# ProtoBricks_4x4.net
KiCad netlist of a schematic drawn in EAGLE
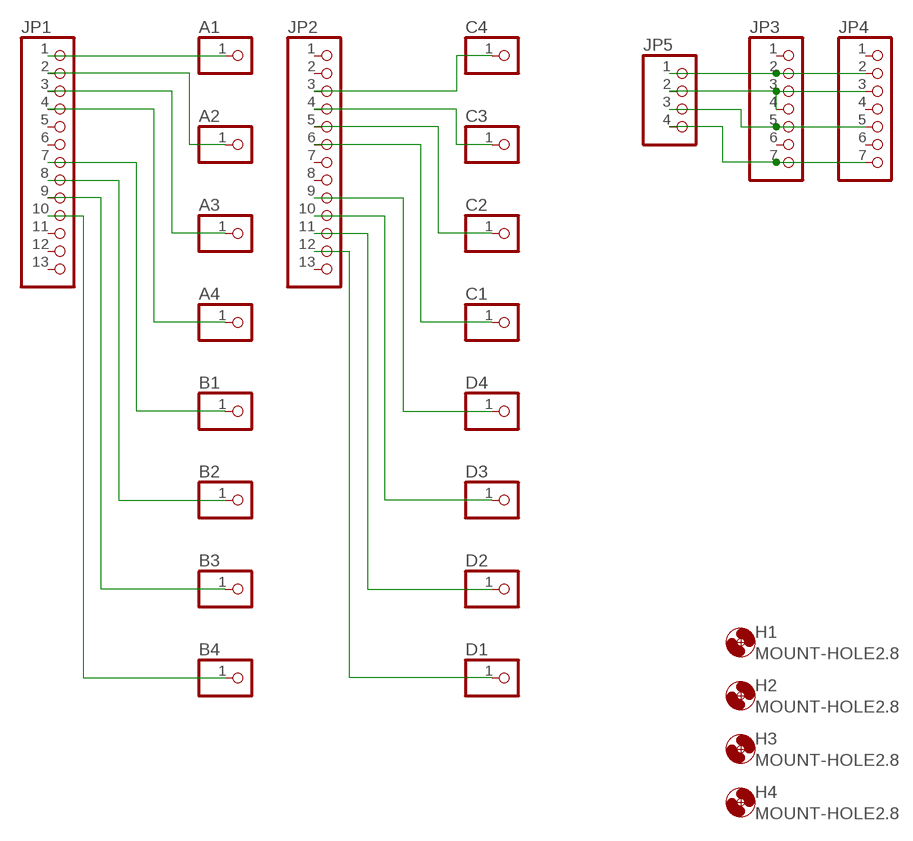
[diagram p0: schematic, sheet 1]

(export (version "E")
  (design (tool "Eeschema 10.0.6"))
  (components
    (comp (ref "A1")
      (value "PINHD-1X1")
      (footprint "eagle-import:1X01")
      (libsource (lib "eagle-import") (part "PINHD-1X1"))
    )
    (comp (ref "A2")
      (value "PINHD-1X1")
      (footprint "eagle-import:1X01")
      (libsource (lib "eagle-import") (part "PINHD-1X1"))
    )
    (comp (ref "A3")
      (value "PINHD-1X1")
      (footprint "eagle-import:1X01")
      (libsource (lib "eagle-import") (part "PINHD-1X1"))
    )
    (comp (ref "A4")
      (value "PINHD-1X1")
      (footprint "eagle-import:1X01")
      (libsource (lib "eagle-import") (part "PINHD-1X1"))
    )
    (comp (ref "B1")
      (value "PINHD-1X1")
      (footprint "eagle-import:1X01")
      (libsource (lib "eagle-import") (part "PINHD-1X1"))
    )
    (comp (ref "B2")
      (value "PINHD-1X1")
      (footprint "eagle-import:1X01")
      (libsource (lib "eagle-import") (part "PINHD-1X1"))
    )
    (comp (ref "B3")
      (value "PINHD-1X1")
      (footprint "eagle-import:1X01")
      (libsource (lib "eagle-import") (part "PINHD-1X1"))
    )
    (comp (ref "B4")
      (value "PINHD-1X1")
      (footprint "eagle-import:1X01")
      (libsource (lib "eagle-import") (part "PINHD-1X1"))
    )
    (comp (ref "C1")
      (value "PINHD-1X1")
      (footprint "eagle-import:1X01")
      (libsource (lib "eagle-import") (part "PINHD-1X1"))
    )
    (comp (ref "C2")
      (value "PINHD-1X1")
      (footprint "eagle-import:1X01")
      (libsource (lib "eagle-import") (part "PINHD-1X1"))
    )
    (comp (ref "C3")
      (value "PINHD-1X1")
      (footprint "eagle-import:1X01")
      (libsource (lib "eagle-import") (part "PINHD-1X1"))
    )
    (comp (ref "C4")
      (value "PINHD-1X1")
      (footprint "eagle-import:1X01")
      (libsource (lib "eagle-import") (part "PINHD-1X1"))
    )
    (comp (ref "D1")
      (value "PINHD-1X1")
      (footprint "eagle-import:1X01")
      (libsource (lib "eagle-import") (part "PINHD-1X1"))
    )
    (comp (ref "D2")
      (value "PINHD-1X1")
      (footprint "eagle-import:1X01")
      (libsource (lib "eagle-import") (part "PINHD-1X1"))
    )
    (comp (ref "D3")
      (value "PINHD-1X1")
      (footprint "eagle-import:1X01")
      (libsource (lib "eagle-import") (part "PINHD-1X1"))
    )
    (comp (ref "D4")
      (value "PINHD-1X1")
      (footprint "eagle-import:1X01")
      (libsource (lib "eagle-import") (part "PINHD-1X1"))
    )
    (comp (ref "H1")
      (value "MOUNT-HOLE2.8")
      (footprint "eagle-import:2,8")
      (libsource (lib "eagle-import") (part "MOUNT-HOLE2.8"))
    )
    (comp (ref "H2")
      (value "MOUNT-HOLE2.8")
      (footprint "eagle-import:2,8")
      (libsource (lib "eagle-import") (part "MOUNT-HOLE2.8"))
    )
    (comp (ref "H3")
      (value "MOUNT-HOLE2.8")
      (footprint "eagle-import:2,8")
      (libsource (lib "eagle-import") (part "MOUNT-HOLE2.8"))
    )
    (comp (ref "H4")
      (value "MOUNT-HOLE2.8")
      (footprint "eagle-import:2,8")
      (libsource (lib "eagle-import") (part "MOUNT-HOLE2.8"))
    )
    (comp (ref "JP1")
      (value "PINHD-1X13")
      (footprint "eagle-import:1X13")
      (libsource (lib "eagle-import") (part "PINHD-1X13"))
    )
    (comp (ref "JP2")
      (value "PINHD-1X13")
      (footprint "eagle-import:1X13")
      (libsource (lib "eagle-import") (part "PINHD-1X13"))
    )
    (comp (ref "JP3")
      (value "PINHD-1X7")
      (footprint "eagle-import:1X07")
      (libsource (lib "eagle-import") (part "PINHD-1X7"))
    )
    (comp (ref "JP4")
      (value "PINHD-1X7")
      (footprint "eagle-import:1X07")
      (libsource (lib "eagle-import") (part "PINHD-1X7"))
    )
    (comp (ref "JP5")
      (value "PINHD-1X4")
      (footprint "eagle-import:1X04")
      (libsource (lib "eagle-import") (part "PINHD-1X4"))
    )
  )
  (nets
    (net (code "1") (name "Net-(A1-Pad1)") (class "Default")
      (node (ref "A1") (pin "1") (pinfunction "1_1") (pintype "passive"))
      (node (ref "JP1") (pin "1") (pinfunction "1_1") (pintype "passive"))
    )
    (net (code "2") (name "Net-(A2-Pad1)") (class "Default")
      (node (ref "A2") (pin "1") (pinfunction "1_1") (pintype "passive"))
      (node (ref "JP1") (pin "2") (pinfunction "2_2") (pintype "passive"))
    )
    (net (code "3") (name "Net-(A3-Pad1)") (class "Default")
      (node (ref "A3") (pin "1") (pinfunction "1_1") (pintype "passive"))
      (node (ref "JP1") (pin "3") (pinfunction "3_3") (pintype "passive"))
    )
    (net (code "4") (name "Net-(A4-Pad1)") (class "Default")
      (node (ref "A4") (pin "1") (pinfunction "1_1") (pintype "passive"))
      (node (ref "JP1") (pin "4") (pinfunction "4_4") (pintype "passive"))
    )
    (net (code "5") (name "Net-(B1-Pad1)") (class "Default")
      (node (ref "B1") (pin "1") (pinfunction "1_1") (pintype "passive"))
      (node (ref "JP1") (pin "7") (pinfunction "7_7") (pintype "passive"))
    )
    (net (code "6") (name "Net-(B2-Pad1)") (class "Default")
      (node (ref "B2") (pin "1") (pinfunction "1_1") (pintype "passive"))
      (node (ref "JP1") (pin "8") (pinfunction "8_8") (pintype "passive"))
    )
    (net (code "7") (name "Net-(B3-Pad1)") (class "Default")
      (node (ref "B3") (pin "1") (pinfunction "1_1") (pintype "passive"))
      (node (ref "JP1") (pin "9") (pinfunction "9_9") (pintype "passive"))
    )
    (net (code "8") (name "Net-(B4-Pad1)") (class "Default")
      (node (ref "B4") (pin "1") (pinfunction "1_1") (pintype "passive"))
      (node (ref "JP1") (pin "10") (pinfunction "10_10") (pintype "passive"))
    )
    (net (code "9") (name "Net-(C1-Pad1)") (class "Default")
      (node (ref "C1") (pin "1") (pinfunction "1_1") (pintype "passive"))
      (node (ref "JP2") (pin "6") (pinfunction "6_6") (pintype "passive"))
    )
    (net (code "10") (name "Net-(C2-Pad1)") (class "Default")
      (node (ref "C2") (pin "1") (pinfunction "1_1") (pintype "passive"))
      (node (ref "JP2") (pin "5") (pinfunction "5_5") (pintype "passive"))
    )
    (net (code "11") (name "Net-(C3-Pad1)") (class "Default")
      (node (ref "C3") (pin "1") (pinfunction "1_1") (pintype "passive"))
      (node (ref "JP2") (pin "4") (pinfunction "4_4") (pintype "passive"))
    )
    (net (code "12") (name "Net-(C4-Pad1)") (class "Default")
      (node (ref "C4") (pin "1") (pinfunction "1_1") (pintype "passive"))
      (node (ref "JP2") (pin "3") (pinfunction "3_3") (pintype "passive"))
    )
    (net (code "13") (name "Net-(D1-Pad1)") (class "Default")
      (node (ref "D1") (pin "1") (pinfunction "1_1") (pintype "passive"))
      (node (ref "JP2") (pin "12") (pinfunction "12_12") (pintype "passive"))
    )
    (net (code "14") (name "Net-(D2-Pad1)") (class "Default")
      (node (ref "D2") (pin "1") (pinfunction "1_1") (pintype "passive"))
      (node (ref "JP2") (pin "11") (pinfunction "11_11") (pintype "passive"))
    )
    (net (code "15") (name "Net-(D3-Pad1)") (class "Default")
      (node (ref "D3") (pin "1") (pinfunction "1_1") (pintype "passive"))
      (node (ref "JP2") (pin "10") (pinfunction "10_10") (pintype "passive"))
    )
    (net (code "16") (name "Net-(D4-Pad1)") (class "Default")
      (node (ref "D4") (pin "1") (pinfunction "1_1") (pintype "passive"))
      (node (ref "JP2") (pin "9") (pinfunction "9_9") (pintype "passive"))
    )
    (net (code "17") (name "Net-(JP3-Pad2)") (class "Default")
      (node (ref "JP3") (pin "2") (pinfunction "2_2") (pintype "passive"))
      (node (ref "JP4") (pin "2") (pinfunction "2_2") (pintype "passive"))
      (node (ref "JP5") (pin "1") (pinfunction "1_1") (pintype "passive"))
    )
    (net (code "18") (name "Net-(JP3-Pad3)") (class "Default")
      (node (ref "JP3") (pin "3") (pinfunction "3_3") (pintype "passive"))
      (node (ref "JP3") (pin "4") (pinfunction "4_4") (pintype "passive"))
      (node (ref "JP4") (pin "3") (pinfunction "3_3") (pintype "passive"))
      (node (ref "JP5") (pin "2") (pinfunction "2_2") (pintype "passive"))
    )
    (net (code "19") (name "Net-(JP3-Pad5)") (class "Default")
      (node (ref "JP3") (pin "5") (pinfunction "5_5") (pintype "passive"))
      (node (ref "JP4") (pin "5") (pinfunction "5_5") (pintype "passive"))
      (node (ref "JP5") (pin "3") (pinfunction "3_3") (pintype "passive"))
    )
    (net (code "20") (name "Net-(JP3-Pad7)") (class "Default")
      (node (ref "JP3") (pin "7") (pinfunction "7_7") (pintype "passive"))
      (node (ref "JP4") (pin "7") (pinfunction "7_7") (pintype "passive"))
      (node (ref "JP5") (pin "4") (pinfunction "4_4") (pintype "passive"))
    )
    (net (code "21") (name "unconnected-(JP1-Pad5)") (class "Default")
      (node (ref "JP1") (pin "5") (pinfunction "5_5") (pintype "passive"))
    )
    (net (code "22") (name "unconnected-(JP1-Pad6)") (class "Default")
      (node (ref "JP1") (pin "6") (pinfunction "6_6") (pintype "passive"))
    )
    (net (code "23") (name "unconnected-(JP1-Pad11)") (class "Default")
      (node (ref "JP1") (pin "11") (pinfunction "11_11") (pintype "passive"))
    )
    (net (code "24") (name "unconnected-(JP1-Pad12)") (class "Default")
      (node (ref "JP1") (pin "12") (pinfunction "12_12") (pintype "passive"))
    )
    (net (code "25") (name "unconnected-(JP1-Pad13)") (class "Default")
      (node (ref "JP1") (pin "13") (pinfunction "13_13") (pintype "passive"))
    )
    (net (code "26") (name "unconnected-(JP2-Pad1)") (class "Default")
      (node (ref "JP2") (pin "1") (pinfunction "1_1") (pintype "passive"))
    )
    (net (code "27") (name "unconnected-(JP2-Pad2)") (class "Default")
      (node (ref "JP2") (pin "2") (pinfunction "2_2") (pintype "passive"))
    )
    (net (code "28") (name "unconnected-(JP2-Pad7)") (class "Default")
      (node (ref "JP2") (pin "7") (pinfunction "7_7") (pintype "passive"))
    )
    (net (code "29") (name "unconnected-(JP2-Pad8)") (class "Default")
      (node (ref "JP2") (pin "8") (pinfunction "8_8") (pintype "passive"))
    )
    (net (code "30") (name "unconnected-(JP2-Pad13)") (class "Default")
      (node (ref "JP2") (pin "13") (pinfunction "13_13") (pintype "passive"))
    )
    (net (code "31") (name "unconnected-(JP3-Pad1)") (class "Default")
      (node (ref "JP3") (pin "1") (pinfunction "1_1") (pintype "passive"))
    )
    (net (code "32") (name "unconnected-(JP3-Pad6)") (class "Default")
      (node (ref "JP3") (pin "6") (pinfunction "6_6") (pintype "passive"))
    )
    (net (code "33") (name "unconnected-(JP4-Pad1)") (class "Default")
      (node (ref "JP4") (pin "1") (pinfunction "1_1") (pintype "passive"))
    )
    (net (code "34") (name "unconnected-(JP4-Pad4)") (class "Default")
      (node (ref "JP4") (pin "4") (pinfunction "4_4") (pintype "passive"))
    )
    (net (code "35") (name "unconnected-(JP4-Pad6)") (class "Default")
      (node (ref "JP4") (pin "6") (pinfunction "6_6") (pintype "passive"))
    )
  )
)
